# Reefing-USB.net
KiCad netlist of a schematic drawn in Altium Designer
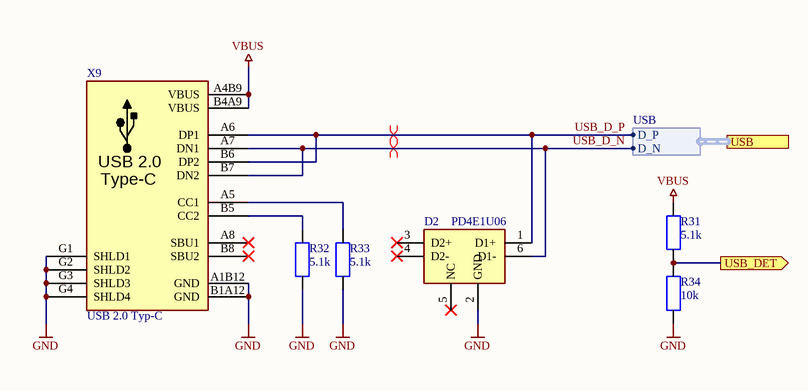
[diagram p0: Reefing-USB.SchDoc]

(export (version "E")
  (design (tool "Eeschema 10.0.6"))
  (components
    (comp (ref "D2")
      (value "PD4E1U06")
      (footprint "SMD IC SOT-363 (SC-70-6)")
      (description "Unidirectional 3A (8/20us) 15V (Typ) 6.5V 5.5V (Max) SOT-363 ESD Protection Devices ROHS")
      (libsource (lib "Fleet-Monitor") (part "PD4E1U06DCKR"))
    )
    (comp (ref "R31")
      (value "5.1k")
      (footprint "SMD Widerstand 0402")
      (description "SMD Chip Resistor E24")
      (libsource (lib "CATS-EUROC") (part "E24 - 5.1k"))
    )
    (comp (ref "R32")
      (value "5.1k")
      (footprint "SMD Widerstand 0402")
      (description "SMD Chip Resistor E24")
      (libsource (lib "Resistors-E24") (part "E24 - 5.1k"))
    )
    (comp (ref "R33")
      (value "5.1k")
      (footprint "SMD Widerstand 0402")
      (description "SMD Chip Resistor E24")
      (libsource (lib "Resistors-E24") (part "E24 - 5.1k"))
    )
    (comp (ref "R34")
      (value "10k")
      (footprint "SMD Widerstand 0402")
      (description "SMD Chip Resistor E24")
      (libsource (lib "CATS-EUROC") (part "E24 - 10k"))
    )
    (comp (ref "X9")
      (value "USB 2.0 Typ-C")
      (footprint "THT USB-C Socket (A40-00119)")
      (description "Typ-C")
      (libsource (lib "Connectors") (part "USB Type-C USB 2.0"))
    )
  )
  (nets
    (net (code "2") (name "/USB_DET") (class "Default")
      (node (ref "R31") (pin "2") (pinfunction "2_2") (pintype "passive"))
      (node (ref "R34") (pin "1") (pinfunction "1_1") (pintype "passive"))
    )
    (net (code "3") (name "/USB_D_N") (class "Default")
      (node (ref "D2") (pin "6") (pinfunction "D1-_6") (pintype "passive"))
      (node (ref "X9") (pin "A7") (pinfunction "DN1_A7") (pintype "passive"))
      (node (ref "X9") (pin "B7") (pinfunction "DN2_B7") (pintype "passive"))
    )
    (net (code "4") (name "/USB_D_P") (class "Default")
      (node (ref "D2") (pin "1") (pinfunction "D1+_1") (pintype "passive"))
      (node (ref "X9") (pin "A6") (pinfunction "DP1_A6") (pintype "passive"))
      (node (ref "X9") (pin "B6") (pinfunction "DP2_B6") (pintype "passive"))
    )
    (net (code "6") (name "GND") (class "Default")
      (node (ref "D2") (pin "2") (pinfunction "GND_2") (pintype "passive"))
      (node (ref "R32") (pin "1") (pinfunction "1_1") (pintype "passive"))
      (node (ref "R33") (pin "1") (pinfunction "1_1") (pintype "passive"))
      (node (ref "R34") (pin "2") (pinfunction "2_2") (pintype "passive"))
      (node (ref "X9") (pin "A1B12") (pinfunction "GND_A1B12") (pintype "passive"))
      (node (ref "X9") (pin "B1A12") (pinfunction "GND_B1A12") (pintype "passive"))
      (node (ref "X9") (pin "G1") (pinfunction "SHLD1_G1") (pintype "passive"))
      (node (ref "X9") (pin "G2") (pinfunction "SHLD2_G2") (pintype "passive"))
      (node (ref "X9") (pin "G3") (pinfunction "SHLD3_G3") (pintype "passive"))
      (node (ref "X9") (pin "G4") (pinfunction "SHLD4_G4") (pintype "passive"))
    )
    (net (code "7") (name "Net-(X9-CC1)") (class "Default")
      (node (ref "R33") (pin "2") (pinfunction "2_2") (pintype "passive"))
      (node (ref "X9") (pin "A5") (pinfunction "CC1_A5") (pintype "passive"))
    )
    (net (code "8") (name "Net-(X9-CC2)") (class "Default")
      (node (ref "R32") (pin "2") (pinfunction "2_2") (pintype "passive"))
      (node (ref "X9") (pin "B5") (pinfunction "CC2_B5") (pintype "passive"))
    )
    (net (code "9") (name "VBUS") (class "Default")
      (node (ref "R31") (pin "1") (pinfunction "1_1") (pintype "passive"))
      (node (ref "X9") (pin "A4B9") (pinfunction "VBUS_A4B9") (pintype "passive"))
      (node (ref "X9") (pin "B4A9") (pinfunction "VBUS_B4A9") (pintype "passive"))
    )
    (net (code "10") (name "unconnected-(D2-D2+-Pad3)") (class "Default")
      (node (ref "D2") (pin "3") (pinfunction "D2+_3") (pintype "passive+no_connect"))
    )
    (net (code "11") (name "unconnected-(D2-D2--Pad4)") (class "Default")
      (node (ref "D2") (pin "4") (pinfunction "D2-_4") (pintype "passive+no_connect"))
    )
    (net (code "12") (name "unconnected-(D2-NC-Pad5)") (class "Default")
      (node (ref "D2") (pin "5") (pinfunction "NC_5") (pintype "passive+no_connect"))
    )
    (net (code "13") (name "unconnected-(X9-SBU1-PadA8)") (class "Default")
      (node (ref "X9") (pin "A8") (pinfunction "SBU1_A8") (pintype "passive+no_connect"))
    )
    (net (code "14") (name "unconnected-(X9-SBU2-PadB8)") (class "Default")
      (node (ref "X9") (pin "B8") (pinfunction "SBU2_B8") (pintype "passive+no_connect"))
    )
  )
)
